# Ponte_-_ArduUri.net
KiCad netlist of a schematic drawn in EAGLE
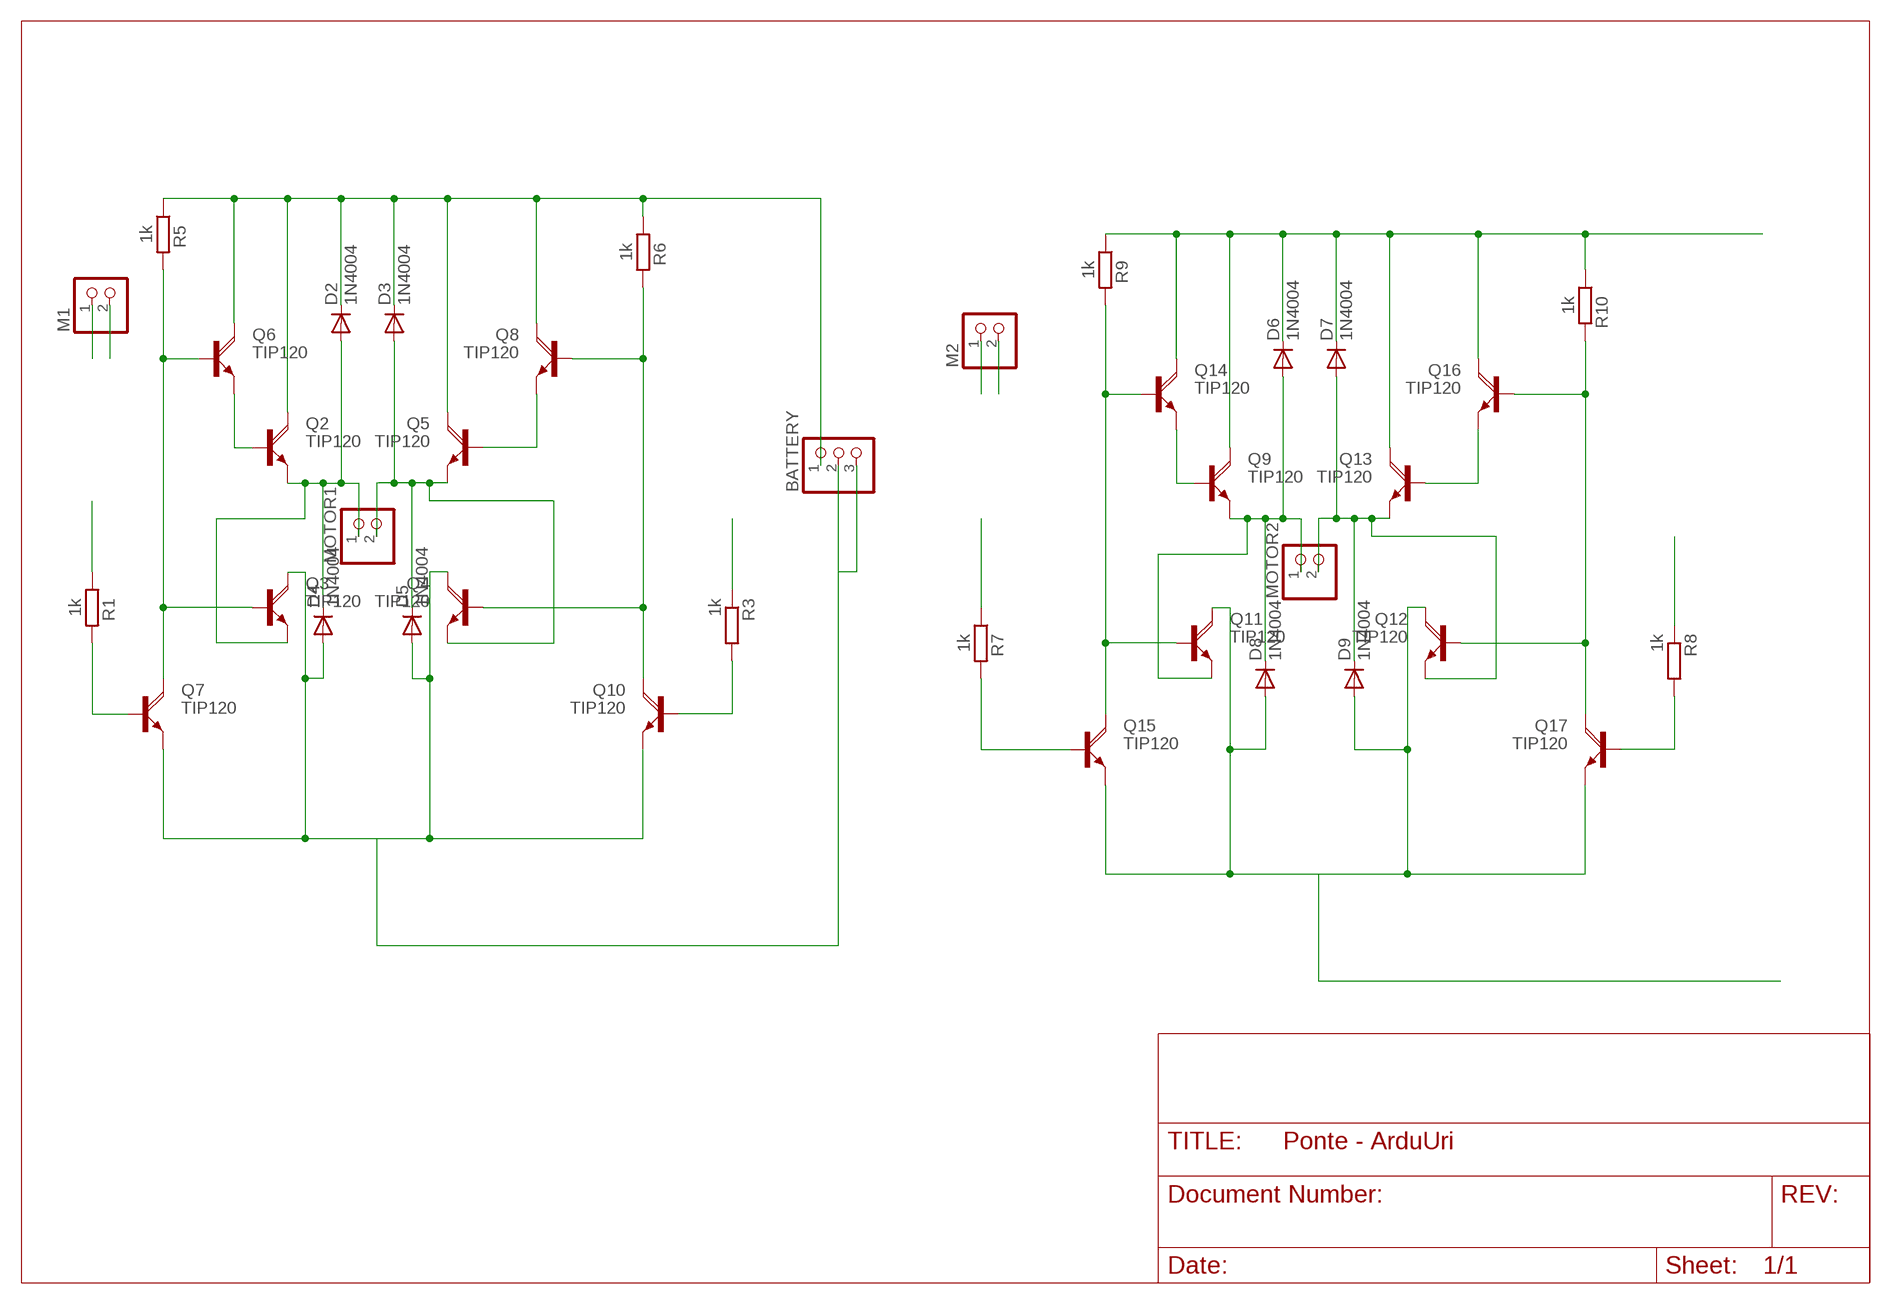
[diagram p0: schematic, sheet 1]

(export (version "E")
  (design (tool "Eeschema 10.0.6"))
  (components
    (comp (ref "BATTERY")
      (value "PINHD-1X3")
      (footprint "eagle-import:1X03")
      (libsource (lib "eagle-import") (part "PINHD-1X3"))
    )
    (comp (ref "D2")
      (value "1N4004")
      (footprint "eagle-import:DO41-10")
      (libsource (lib "eagle-import") (part "1N4004"))
    )
    (comp (ref "D3")
      (value "1N4004")
      (footprint "eagle-import:DO41-10")
      (libsource (lib "eagle-import") (part "1N4004"))
    )
    (comp (ref "D4")
      (value "1N4004")
      (footprint "eagle-import:DO41-10")
      (libsource (lib "eagle-import") (part "1N4004"))
    )
    (comp (ref "D5")
      (value "1N4004")
      (footprint "eagle-import:DO41-10")
      (libsource (lib "eagle-import") (part "1N4004"))
    )
    (comp (ref "D6")
      (value "1N4004")
      (footprint "eagle-import:DO41-10")
      (libsource (lib "eagle-import") (part "1N4004"))
    )
    (comp (ref "D7")
      (value "1N4004")
      (footprint "eagle-import:DO41-10")
      (libsource (lib "eagle-import") (part "1N4004"))
    )
    (comp (ref "D8")
      (value "1N4004")
      (footprint "eagle-import:DO41-10")
      (libsource (lib "eagle-import") (part "1N4004"))
    )
    (comp (ref "D9")
      (value "1N4004")
      (footprint "eagle-import:DO41-10")
      (libsource (lib "eagle-import") (part "1N4004"))
    )
    (comp (ref "M1")
      (value "PINHD-1X2")
      (footprint "eagle-import:1X02")
      (libsource (lib "eagle-import") (part "PINHD-1X2"))
    )
    (comp (ref "M2")
      (value "PINHD-1X2")
      (footprint "eagle-import:1X02")
      (libsource (lib "eagle-import") (part "PINHD-1X2"))
    )
    (comp (ref "MOTOR1")
      (value "PINHD-1X2")
      (footprint "eagle-import:1X02")
      (libsource (lib "eagle-import") (part "PINHD-1X2"))
    )
    (comp (ref "MOTOR2")
      (value "PINHD-1X2")
      (footprint "eagle-import:1X02")
      (libsource (lib "eagle-import") (part "PINHD-1X2"))
    )
    (comp (ref "Q2")
      (value "TIP120")
      (footprint "eagle-import:TO220AH")
      (libsource (lib "eagle-import") (part "TIP120"))
    )
    (comp (ref "Q3")
      (value "TIP120")
      (footprint "eagle-import:TO220AH")
      (libsource (lib "eagle-import") (part "TIP120"))
    )
    (comp (ref "Q4")
      (value "TIP120")
      (footprint "eagle-import:TO220AH")
      (libsource (lib "eagle-import") (part "TIP120"))
    )
    (comp (ref "Q5")
      (value "TIP120")
      (footprint "eagle-import:TO220AH")
      (libsource (lib "eagle-import") (part "TIP120"))
    )
    (comp (ref "Q6")
      (value "TIP120")
      (footprint "eagle-import:TO220AH")
      (libsource (lib "eagle-import") (part "TIP120"))
    )
    (comp (ref "Q7")
      (value "TIP120")
      (footprint "eagle-import:TO220AH")
      (libsource (lib "eagle-import") (part "TIP120"))
    )
    (comp (ref "Q8")
      (value "TIP120")
      (footprint "eagle-import:TO220AH")
      (libsource (lib "eagle-import") (part "TIP120"))
    )
    (comp (ref "Q9")
      (value "TIP120")
      (footprint "eagle-import:TO220AH")
      (libsource (lib "eagle-import") (part "TIP120"))
    )
    (comp (ref "Q10")
      (value "TIP120")
      (footprint "eagle-import:TO220AH")
      (libsource (lib "eagle-import") (part "TIP120"))
    )
    (comp (ref "Q11")
      (value "TIP120")
      (footprint "eagle-import:TO220AH")
      (libsource (lib "eagle-import") (part "TIP120"))
    )
    (comp (ref "Q12")
      (value "TIP120")
      (footprint "eagle-import:TO220AH")
      (libsource (lib "eagle-import") (part "TIP120"))
    )
    (comp (ref "Q13")
      (value "TIP120")
      (footprint "eagle-import:TO220AH")
      (libsource (lib "eagle-import") (part "TIP120"))
    )
    (comp (ref "Q14")
      (value "TIP120")
      (footprint "eagle-import:TO220AH")
      (libsource (lib "eagle-import") (part "TIP120"))
    )
    (comp (ref "Q15")
      (value "TIP120")
      (footprint "eagle-import:TO220AH")
      (libsource (lib "eagle-import") (part "TIP120"))
    )
    (comp (ref "Q16")
      (value "TIP120")
      (footprint "eagle-import:TO220AH")
      (libsource (lib "eagle-import") (part "TIP120"))
    )
    (comp (ref "Q17")
      (value "TIP120")
      (footprint "eagle-import:TO220AH")
      (libsource (lib "eagle-import") (part "TIP120"))
    )
    (comp (ref "R1")
      (value "1k")
      (footprint "eagle-import:0204_7")
      (libsource (lib "eagle-import") (part "R-EU_0204/7"))
    )
    (comp (ref "R3")
      (value "1k")
      (footprint "eagle-import:0204_7")
      (libsource (lib "eagle-import") (part "R-EU_0204/7"))
    )
    (comp (ref "R5")
      (value "1k")
      (footprint "eagle-import:0204_7")
      (libsource (lib "eagle-import") (part "R-EU_0204/7"))
    )
    (comp (ref "R6")
      (value "1k")
      (footprint "eagle-import:0204_7")
      (libsource (lib "eagle-import") (part "R-EU_0204/7"))
    )
    (comp (ref "R7")
      (value "1k")
      (footprint "eagle-import:0204_7")
      (libsource (lib "eagle-import") (part "R-EU_0204/7"))
    )
    (comp (ref "R8")
      (value "1k")
      (footprint "eagle-import:0204_7")
      (libsource (lib "eagle-import") (part "R-EU_0204/7"))
    )
    (comp (ref "R9")
      (value "1k")
      (footprint "eagle-import:0204_7")
      (libsource (lib "eagle-import") (part "R-EU_0204/7"))
    )
    (comp (ref "R10")
      (value "1k")
      (footprint "eagle-import:0204_7")
      (libsource (lib "eagle-import") (part "R-EU_0204/7"))
    )
  )
  (nets
    (net (code "1") (name "/GND") (class "Default")
      (node (ref "BATTERY") (pin "2") (pinfunction "2_2") (pintype "passive"))
      (node (ref "BATTERY") (pin "3") (pinfunction "3_3") (pintype "passive"))
      (node (ref "D4") (pin "A") (pinfunction "A_A") (pintype "passive"))
      (node (ref "D5") (pin "A") (pinfunction "A_A") (pintype "passive"))
      (node (ref "D8") (pin "A") (pinfunction "A_A") (pintype "passive"))
      (node (ref "D9") (pin "A") (pinfunction "A_A") (pintype "passive"))
      (node (ref "Q10") (pin "E") (pinfunction "E_E") (pintype "passive"))
      (node (ref "Q11") (pin "C") (pinfunction "C_C") (pintype "passive"))
      (node (ref "Q12") (pin "C") (pinfunction "C_C") (pintype "passive"))
      (node (ref "Q15") (pin "E") (pinfunction "E_E") (pintype "passive"))
      (node (ref "Q17") (pin "E") (pinfunction "E_E") (pintype "passive"))
      (node (ref "Q3") (pin "C") (pinfunction "C_C") (pintype "passive"))
      (node (ref "Q4") (pin "C") (pinfunction "C_C") (pintype "passive"))
      (node (ref "Q7") (pin "E") (pinfunction "E_E") (pintype "passive"))
    )
    (net (code "2") (name "/M1-A1") (class "Default")
      (node (ref "M1") (pin "1") (pinfunction "1_1") (pintype "passive"))
      (node (ref "R1") (pin "1") (pinfunction "1_1") (pintype "passive"))
    )
    (net (code "3") (name "/M1-B1") (class "Default")
      (node (ref "M1") (pin "2") (pinfunction "2_2") (pintype "passive"))
      (node (ref "R3") (pin "1") (pinfunction "1_1") (pintype "passive"))
    )
    (net (code "4") (name "/M2-A2") (class "Default")
      (node (ref "M2") (pin "1") (pinfunction "1_1") (pintype "passive"))
      (node (ref "R7") (pin "1") (pinfunction "1_1") (pintype "passive"))
    )
    (net (code "5") (name "/M2-B2") (class "Default")
      (node (ref "M2") (pin "2") (pinfunction "2_2") (pintype "passive"))
      (node (ref "R8") (pin "1") (pinfunction "1_1") (pintype "passive"))
    )
    (net (code "6") (name "/VCC-BAT") (class "Default")
      (node (ref "BATTERY") (pin "1") (pinfunction "1_1") (pintype "passive"))
      (node (ref "D2") (pin "C") (pinfunction "C_C") (pintype "passive"))
      (node (ref "D3") (pin "C") (pinfunction "C_C") (pintype "passive"))
      (node (ref "D6") (pin "C") (pinfunction "C_C") (pintype "passive"))
      (node (ref "D7") (pin "C") (pinfunction "C_C") (pintype "passive"))
      (node (ref "Q13") (pin "C") (pinfunction "C_C") (pintype "passive"))
      (node (ref "Q14") (pin "C") (pinfunction "C_C") (pintype "passive"))
      (node (ref "Q16") (pin "C") (pinfunction "C_C") (pintype "passive"))
      (node (ref "Q2") (pin "C") (pinfunction "C_C") (pintype "passive"))
      (node (ref "Q5") (pin "C") (pinfunction "C_C") (pintype "passive"))
      (node (ref "Q6") (pin "C") (pinfunction "C_C") (pintype "passive"))
      (node (ref "Q8") (pin "C") (pinfunction "C_C") (pintype "passive"))
      (node (ref "Q9") (pin "C") (pinfunction "C_C") (pintype "passive"))
      (node (ref "R10") (pin "1") (pinfunction "1_1") (pintype "passive"))
      (node (ref "R5") (pin "1") (pinfunction "1_1") (pintype "passive"))
      (node (ref "R6") (pin "1") (pinfunction "1_1") (pintype "passive"))
      (node (ref "R9") (pin "1") (pinfunction "1_1") (pintype "passive"))
    )
    (net (code "7") (name "Net-(D2-PadA)") (class "Default")
      (node (ref "D2") (pin "A") (pinfunction "A_A") (pintype "passive"))
      (node (ref "D4") (pin "C") (pinfunction "C_C") (pintype "passive"))
      (node (ref "MOTOR1") (pin "1") (pinfunction "1_1") (pintype "passive"))
      (node (ref "Q2") (pin "E") (pinfunction "E_E") (pintype "passive"))
      (node (ref "Q3") (pin "E") (pinfunction "E_E") (pintype "passive"))
    )
    (net (code "8") (name "Net-(D3-PadA)") (class "Default")
      (node (ref "D3") (pin "A") (pinfunction "A_A") (pintype "passive"))
      (node (ref "D5") (pin "C") (pinfunction "C_C") (pintype "passive"))
      (node (ref "MOTOR1") (pin "2") (pinfunction "2_2") (pintype "passive"))
      (node (ref "Q4") (pin "E") (pinfunction "E_E") (pintype "passive"))
      (node (ref "Q5") (pin "E") (pinfunction "E_E") (pintype "passive"))
    )
    (net (code "9") (name "Net-(D6-PadA)") (class "Default")
      (node (ref "D6") (pin "A") (pinfunction "A_A") (pintype "passive"))
      (node (ref "D8") (pin "C") (pinfunction "C_C") (pintype "passive"))
      (node (ref "MOTOR2") (pin "1") (pinfunction "1_1") (pintype "passive"))
      (node (ref "Q11") (pin "E") (pinfunction "E_E") (pintype "passive"))
      (node (ref "Q9") (pin "E") (pinfunction "E_E") (pintype "passive"))
    )
    (net (code "10") (name "Net-(D7-PadA)") (class "Default")
      (node (ref "D7") (pin "A") (pinfunction "A_A") (pintype "passive"))
      (node (ref "D9") (pin "C") (pinfunction "C_C") (pintype "passive"))
      (node (ref "MOTOR2") (pin "2") (pinfunction "2_2") (pintype "passive"))
      (node (ref "Q12") (pin "E") (pinfunction "E_E") (pintype "passive"))
      (node (ref "Q13") (pin "E") (pinfunction "E_E") (pintype "passive"))
    )
    (net (code "11") (name "Net-(Q2-PadB)") (class "Default")
      (node (ref "Q2") (pin "B") (pinfunction "B_B") (pintype "passive"))
      (node (ref "Q6") (pin "E") (pinfunction "E_E") (pintype "passive"))
    )
    (net (code "12") (name "Net-(Q3-PadB)") (class "Default")
      (node (ref "Q3") (pin "B") (pinfunction "B_B") (pintype "passive"))
      (node (ref "Q6") (pin "B") (pinfunction "B_B") (pintype "passive"))
      (node (ref "Q7") (pin "C") (pinfunction "C_C") (pintype "passive"))
      (node (ref "R5") (pin "2") (pinfunction "2_2") (pintype "passive"))
    )
    (net (code "13") (name "Net-(Q5-PadB)") (class "Default")
      (node (ref "Q5") (pin "B") (pinfunction "B_B") (pintype "passive"))
      (node (ref "Q8") (pin "E") (pinfunction "E_E") (pintype "passive"))
    )
    (net (code "14") (name "Net-(Q7-PadB)") (class "Default")
      (node (ref "Q7") (pin "B") (pinfunction "B_B") (pintype "passive"))
      (node (ref "R1") (pin "2") (pinfunction "2_2") (pintype "passive"))
    )
    (net (code "15") (name "Net-(Q10-PadB)") (class "Default")
      (node (ref "Q10") (pin "B") (pinfunction "B_B") (pintype "passive"))
      (node (ref "R3") (pin "2") (pinfunction "2_2") (pintype "passive"))
    )
    (net (code "16") (name "Net-(Q10-PadC)") (class "Default")
      (node (ref "Q10") (pin "C") (pinfunction "C_C") (pintype "passive"))
      (node (ref "Q4") (pin "B") (pinfunction "B_B") (pintype "passive"))
      (node (ref "Q8") (pin "B") (pinfunction "B_B") (pintype "passive"))
      (node (ref "R6") (pin "2") (pinfunction "2_2") (pintype "passive"))
    )
    (net (code "17") (name "Net-(Q11-PadB)") (class "Default")
      (node (ref "Q11") (pin "B") (pinfunction "B_B") (pintype "passive"))
      (node (ref "Q14") (pin "B") (pinfunction "B_B") (pintype "passive"))
      (node (ref "Q15") (pin "C") (pinfunction "C_C") (pintype "passive"))
      (node (ref "R9") (pin "2") (pinfunction "2_2") (pintype "passive"))
    )
    (net (code "18") (name "Net-(Q12-PadB)") (class "Default")
      (node (ref "Q12") (pin "B") (pinfunction "B_B") (pintype "passive"))
      (node (ref "Q16") (pin "B") (pinfunction "B_B") (pintype "passive"))
      (node (ref "Q17") (pin "C") (pinfunction "C_C") (pintype "passive"))
      (node (ref "R10") (pin "2") (pinfunction "2_2") (pintype "passive"))
    )
    (net (code "19") (name "Net-(Q13-PadB)") (class "Default")
      (node (ref "Q13") (pin "B") (pinfunction "B_B") (pintype "passive"))
      (node (ref "Q16") (pin "E") (pinfunction "E_E") (pintype "passive"))
    )
    (net (code "20") (name "Net-(Q14-PadE)") (class "Default")
      (node (ref "Q14") (pin "E") (pinfunction "E_E") (pintype "passive"))
      (node (ref "Q9") (pin "B") (pinfunction "B_B") (pintype "passive"))
    )
    (net (code "21") (name "Net-(Q15-PadB)") (class "Default")
      (node (ref "Q15") (pin "B") (pinfunction "B_B") (pintype "passive"))
      (node (ref "R7") (pin "2") (pinfunction "2_2") (pintype "passive"))
    )
    (net (code "22") (name "Net-(Q17-PadB)") (class "Default")
      (node (ref "Q17") (pin "B") (pinfunction "B_B") (pintype "passive"))
      (node (ref "R8") (pin "2") (pinfunction "2_2") (pintype "passive"))
    )
  )
)
